# BALANCING_IC.net
KiCad netlist of a schematic drawn in Altium Designer
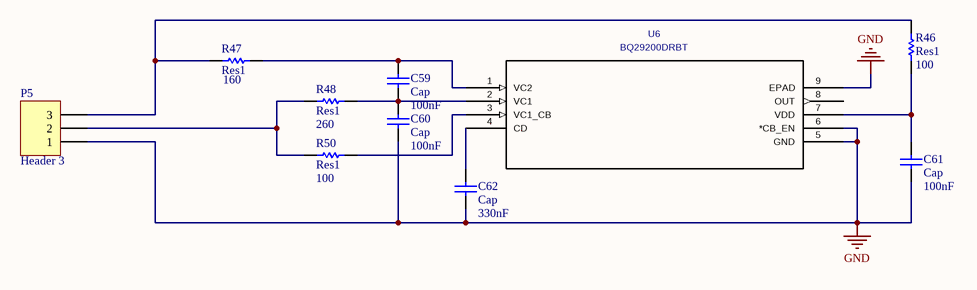
[diagram p0: BALANCING IC.SchDoc]

(export (version "E")
  (design (tool "Eeschema 10.0.6"))
  (components
    (comp (ref "C59")
      (value "Cap")
      (footprint "0402-A")
      (description "Capacitor")
      (fields (field (name "ALTIUM_VALUE") "100nF") (field (name "PUBLISHER") "Altium Limited"))
      (libsource (lib "Miscellaneous Devices") (part "Cap"))
    )
    (comp (ref "C60")
      (value "Cap")
      (footprint "0402-A")
      (description "Capacitor")
      (fields (field (name "ALTIUM_VALUE") "100nF") (field (name "PUBLISHER") "Altium Limited"))
      (libsource (lib "Miscellaneous Devices") (part "Cap"))
    )
    (comp (ref "C61")
      (value "Cap")
      (footprint "0402-A")
      (description "Capacitor")
      (fields (field (name "ALTIUM_VALUE") "100nF") (field (name "PUBLISHER") "Altium Limited"))
      (libsource (lib "Miscellaneous Devices") (part "Cap"))
    )
    (comp (ref "C62")
      (value "Cap")
      (footprint "6-0805_M")
      (description "Capacitor")
      (fields (field (name "ALTIUM_VALUE") "330nF") (field (name "PUBLISHER") "Altium Limited"))
      (libsource (lib "Miscellaneous Devices") (part "Cap"))
    )
    (comp (ref "P5")
      (value "Header 3")
      (footprint "conn3_2-1445050-3_TEC")
      (description "Header, 3-Pin")
      (fields (field (name "PUBLISHER") "Altium Limited"))
      (libsource (lib "Miscellaneous Connectors") (part "Header 3"))
    )
    (comp (ref "R46")
      (value "Res1")
      (footprint "0402-A")
      (description "Resistor")
      (fields (field (name "ALTIUM_VALUE") "100") (field (name "PUBLISHER") "Altium Limited"))
      (libsource (lib "Miscellaneous Devices") (part "Res1"))
    )
    (comp (ref "R47")
      (value "Res1")
      (footprint "0402-A")
      (description "Resistor")
      (fields (field (name "ALTIUM_VALUE") "160") (field (name "PUBLISHER") "Altium Limited"))
      (libsource (lib "Miscellaneous Devices") (part "Res1"))
    )
    (comp (ref "R48")
      (value "Res1")
      (footprint "0402-A")
      (description "Resistor")
      (fields (field (name "ALTIUM_VALUE") "260") (field (name "PUBLISHER") "Altium Limited"))
      (libsource (lib "Miscellaneous Devices") (part "Res1"))
    )
    (comp (ref "R50")
      (value "Res1")
      (footprint "0402-A")
      (description "Resistor")
      (fields (field (name "ALTIUM_VALUE") "100") (field (name "PUBLISHER") "Altium Limited"))
      (libsource (lib "Miscellaneous Devices") (part "Res1"))
    )
    (comp (ref "U6")
      (value "BQ29200DRBT")
      (footprint "DRB8_1P6X2P4")
      (fields (field (name "MANUFACTURER") "Texas Instruments"))
      (libsource (lib "AltiumV15") (part "BQ29200DRBT"))
    )
  )
  (nets
    (net (code "1") (name "GND") (class "Default")
      (node (ref "C60") (pin "1") (pinfunction "1_1") (pintype "passive"))
      (node (ref "C61") (pin "2") (pinfunction "2_2") (pintype "passive"))
      (node (ref "C62") (pin "1") (pinfunction "1_1") (pintype "passive"))
      (node (ref "P5") (pin "1") (pinfunction "1_1") (pintype "passive"))
      (node (ref "U6") (pin "5") (pinfunction "GND_5") (pintype "power_in"))
      (node (ref "U6") (pin "6") (pinfunction "*CB_EN_6") (pintype "passive"))
      (node (ref "U6") (pin "9") (pinfunction "EPAD_9") (pintype "power_in"))
    )
    (net (code "2") (name "Net-(P5-Pad2)") (class "Default")
      (node (ref "P5") (pin "2") (pinfunction "2_2") (pintype "passive"))
      (node (ref "R48") (pin "1") (pinfunction "1_1") (pintype "passive"))
      (node (ref "R50") (pin "1") (pinfunction "1_1") (pintype "passive"))
    )
    (net (code "3") (name "Net-(P5-Pad3)") (class "Default")
      (node (ref "P5") (pin "3") (pinfunction "3_3") (pintype "passive"))
      (node (ref "R46") (pin "1") (pinfunction "1_1") (pintype "passive"))
      (node (ref "R47") (pin "1") (pinfunction "1_1") (pintype "passive"))
    )
    (net (code "4") (name "Net-(U6-CD)") (class "Default")
      (node (ref "C62") (pin "2") (pinfunction "2_2") (pintype "passive"))
      (node (ref "U6") (pin "4") (pinfunction "CD_4") (pintype "passive"))
    )
    (net (code "5") (name "Net-(U6-VC1)") (class "Default")
      (node (ref "C59") (pin "2") (pinfunction "2_2") (pintype "passive"))
      (node (ref "C60") (pin "2") (pinfunction "2_2") (pintype "passive"))
      (node (ref "R48") (pin "2") (pinfunction "2_2") (pintype "passive"))
      (node (ref "U6") (pin "2") (pinfunction "VC1_2") (pintype "input"))
    )
    (net (code "6") (name "Net-(U6-VC1_CB)") (class "Default")
      (node (ref "R50") (pin "2") (pinfunction "2_2") (pintype "passive"))
      (node (ref "U6") (pin "3") (pinfunction "VC1_CB_3") (pintype "input"))
    )
    (net (code "7") (name "Net-(U6-VC2)") (class "Default")
      (node (ref "C59") (pin "1") (pinfunction "1_1") (pintype "passive"))
      (node (ref "R47") (pin "2") (pinfunction "2_2") (pintype "passive"))
      (node (ref "U6") (pin "1") (pinfunction "VC2_1") (pintype "input"))
    )
    (net (code "8") (name "Net-(U6-VDD)") (class "Default")
      (node (ref "C61") (pin "1") (pinfunction "1_1") (pintype "passive"))
      (node (ref "R46") (pin "2") (pinfunction "2_2") (pintype "passive"))
      (node (ref "U6") (pin "7") (pinfunction "VDD_7") (pintype "power_in"))
    )
    (net (code "9") (name "unconnected-(U6-OUT-Pad8)") (class "Default")
      (node (ref "U6") (pin "8") (pinfunction "OUT_8") (pintype "output"))
    )
  )
)
